# RoPi_2560_0_3.net
KiCad netlist of a schematic drawn in EAGLE
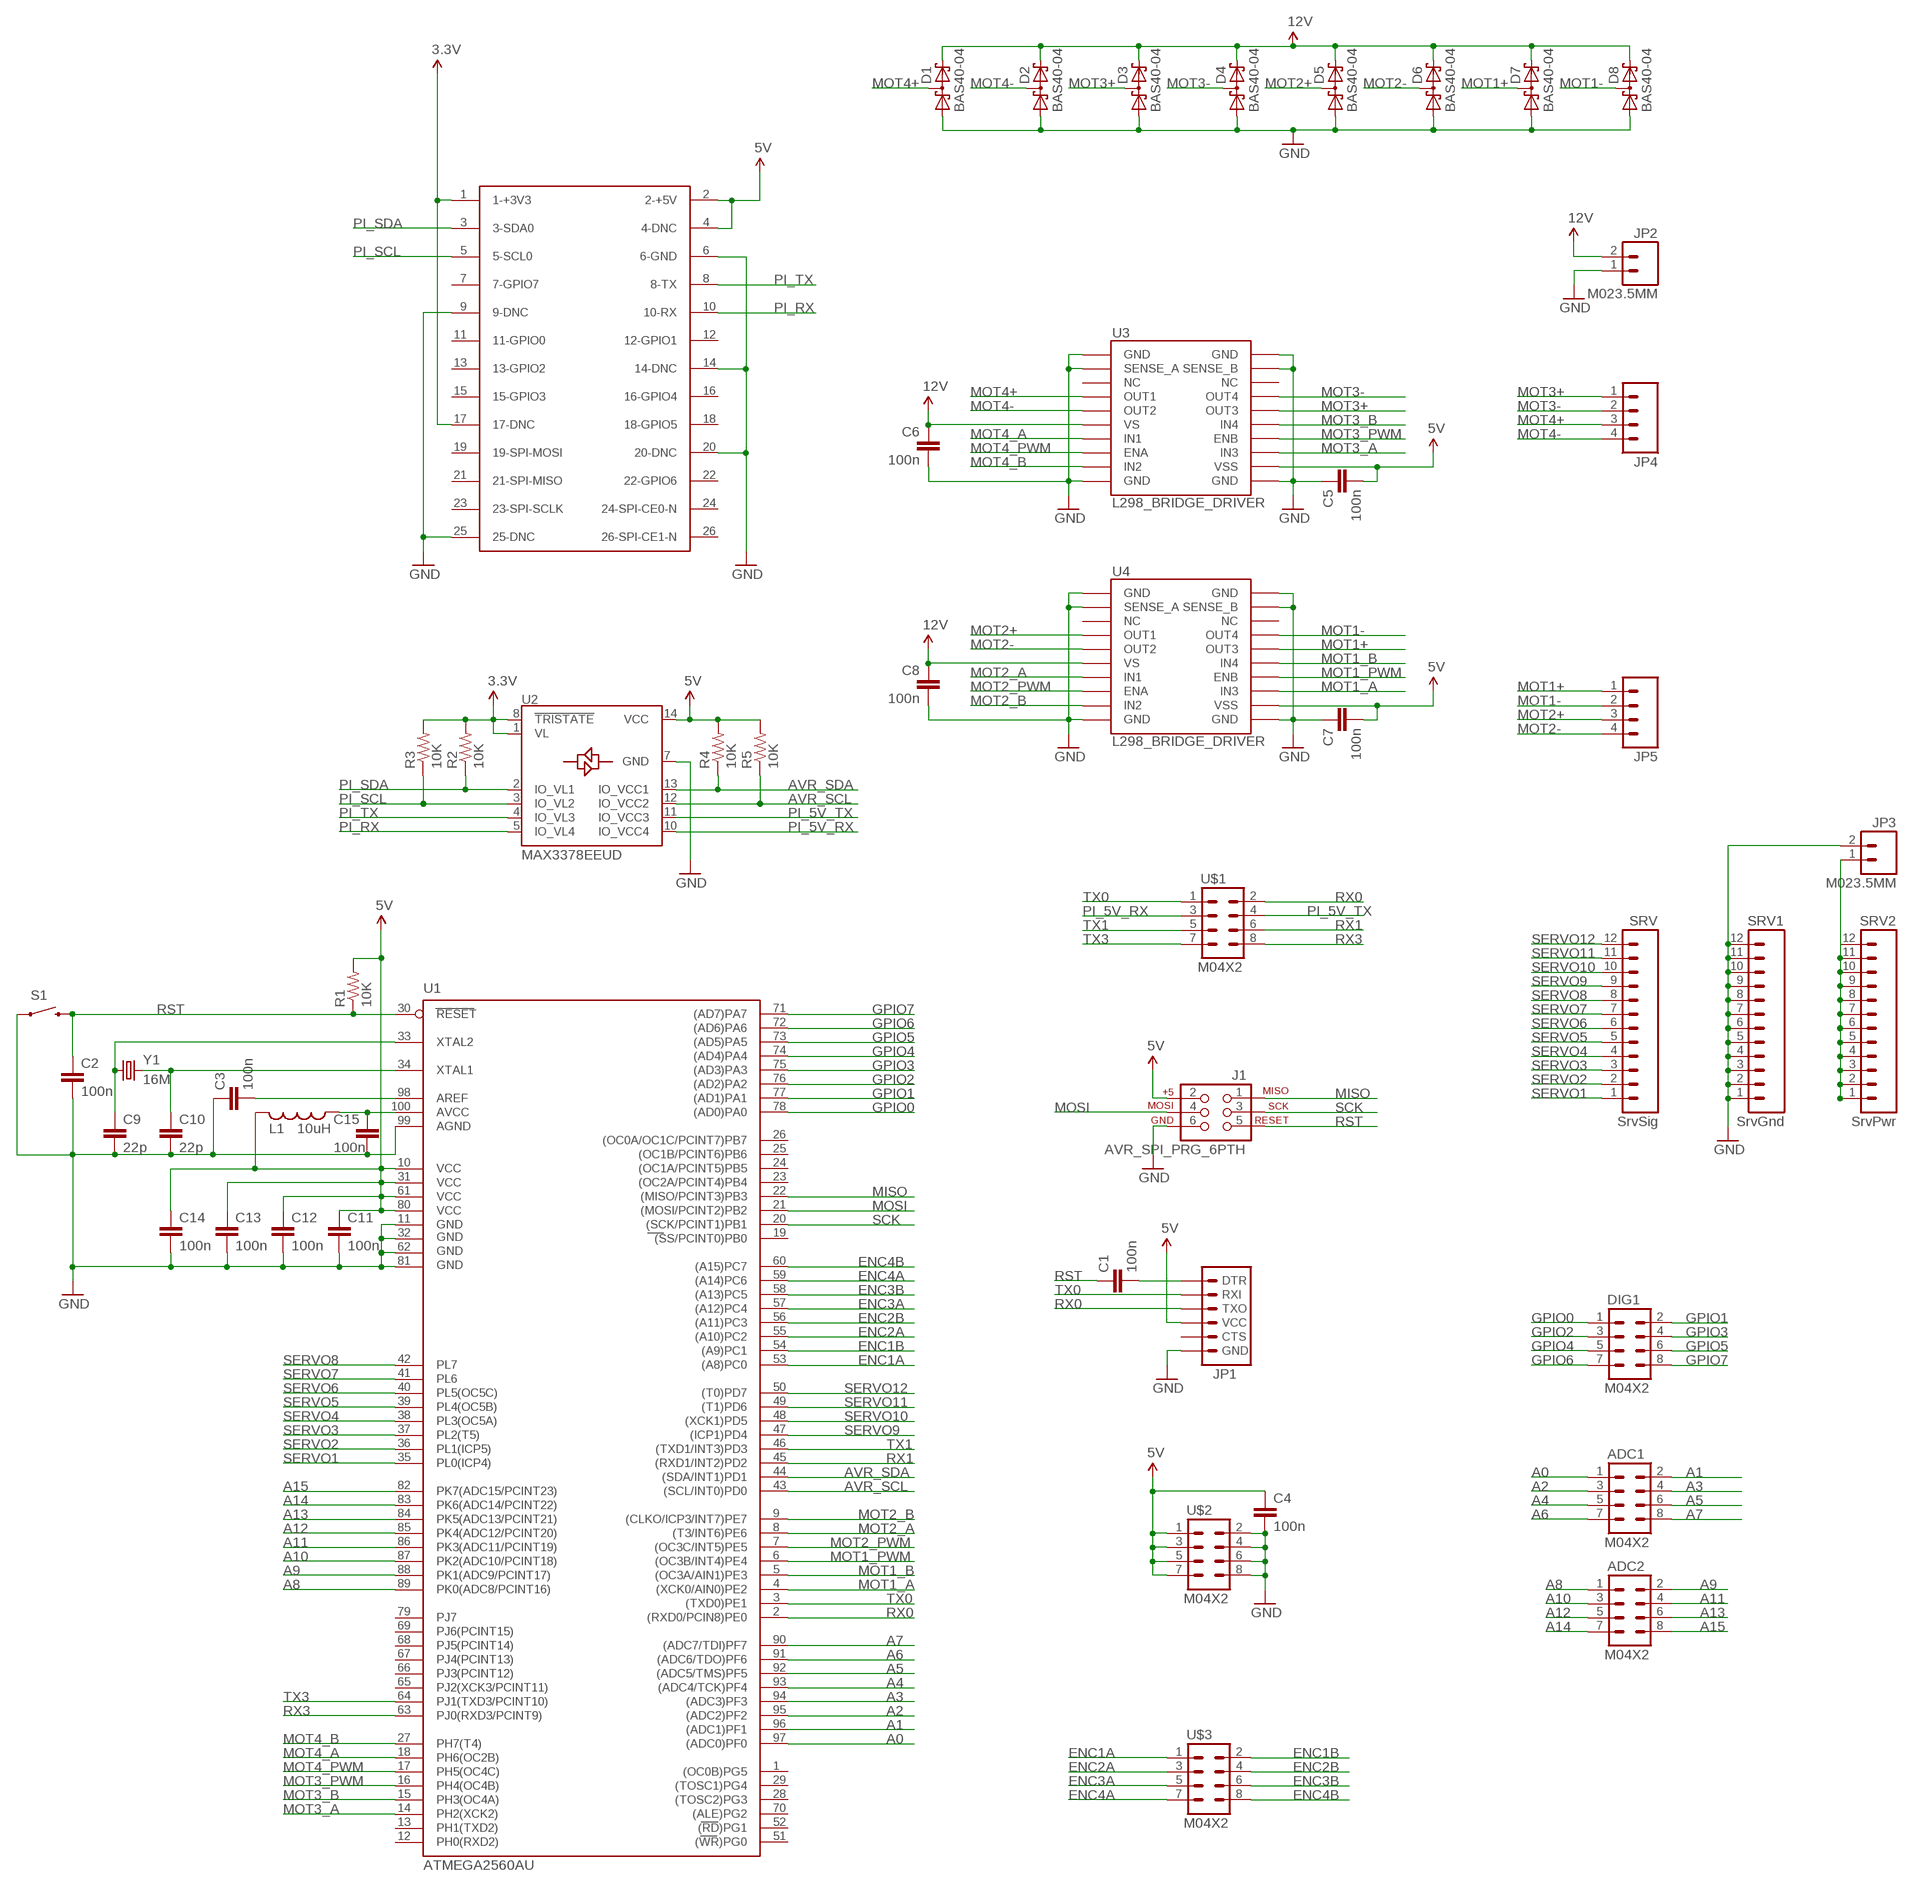
[diagram p0: schematic, sheet 1]

(export (version "E")
  (design (tool "Eeschema 10.0.6"))
  (components
    (comp (ref "ADC1")
      (value "M04X2")
      (footprint "eagle-import:2X4")
      (libsource (lib "eagle-import") (part "M04X2"))
    )
    (comp (ref "ADC2")
      (value "M04X2")
      (footprint "eagle-import:2X4")
      (libsource (lib "eagle-import") (part "M04X2"))
    )
    (comp (ref "C1")
      (value "100n")
      (footprint "eagle-import:0603-CAP")
      (libsource (lib "eagle-import") (part "CAP0603-CAP"))
    )
    (comp (ref "C2")
      (value "100n")
      (footprint "eagle-import:0603-CAP")
      (libsource (lib "eagle-import") (part "CAP0603-CAP"))
    )
    (comp (ref "C3")
      (value "100n")
      (footprint "eagle-import:0603-CAP")
      (libsource (lib "eagle-import") (part "CAP0603-CAP"))
    )
    (comp (ref "C4")
      (value "100n")
      (footprint "eagle-import:0603-CAP")
      (libsource (lib "eagle-import") (part "CAP0603-CAP"))
    )
    (comp (ref "C5")
      (value "100n")
      (footprint "eagle-import:0603-CAP")
      (libsource (lib "eagle-import") (part "CAP0603-CAP"))
    )
    (comp (ref "C6")
      (value "100n")
      (footprint "eagle-import:0603-CAP")
      (libsource (lib "eagle-import") (part "CAP0603-CAP"))
    )
    (comp (ref "C7")
      (value "100n")
      (footprint "eagle-import:0603-CAP")
      (libsource (lib "eagle-import") (part "CAP0603-CAP"))
    )
    (comp (ref "C8")
      (value "100n")
      (footprint "eagle-import:0603-CAP")
      (libsource (lib "eagle-import") (part "CAP0603-CAP"))
    )
    (comp (ref "C9")
      (value "22p")
      (footprint "eagle-import:0603-CAP")
      (libsource (lib "eagle-import") (part "CAP0603-CAP"))
    )
    (comp (ref "C10")
      (value "22p")
      (footprint "eagle-import:0603-CAP")
      (libsource (lib "eagle-import") (part "CAP0603-CAP"))
    )
    (comp (ref "C11")
      (value "100n")
      (footprint "eagle-import:0603-CAP")
      (libsource (lib "eagle-import") (part "CAP0603-CAP"))
    )
    (comp (ref "C12")
      (value "100n")
      (footprint "eagle-import:0603-CAP")
      (libsource (lib "eagle-import") (part "CAP0603-CAP"))
    )
    (comp (ref "C13")
      (value "100n")
      (footprint "eagle-import:0603-CAP")
      (libsource (lib "eagle-import") (part "CAP0603-CAP"))
    )
    (comp (ref "C14")
      (value "100n")
      (footprint "eagle-import:0603-CAP")
      (libsource (lib "eagle-import") (part "CAP0603-CAP"))
    )
    (comp (ref "C15")
      (value "100n")
      (footprint "eagle-import:0603-CAP")
      (libsource (lib "eagle-import") (part "CAP0603-CAP"))
    )
    (comp (ref "D1")
      (value "BAS40-04")
      (footprint "eagle-import:SOT23")
      (libsource (lib "eagle-import") (part "BAS40-04"))
    )
    (comp (ref "D2")
      (value "BAS40-04")
      (footprint "eagle-import:SOT23")
      (libsource (lib "eagle-import") (part "BAS40-04"))
    )
    (comp (ref "D3")
      (value "BAS40-04")
      (footprint "eagle-import:SOT23")
      (libsource (lib "eagle-import") (part "BAS40-04"))
    )
    (comp (ref "D4")
      (value "BAS40-04")
      (footprint "eagle-import:SOT23")
      (libsource (lib "eagle-import") (part "BAS40-04"))
    )
    (comp (ref "D5")
      (value "BAS40-04")
      (footprint "eagle-import:SOT23")
      (libsource (lib "eagle-import") (part "BAS40-04"))
    )
    (comp (ref "D6")
      (value "BAS40-04")
      (footprint "eagle-import:SOT23")
      (libsource (lib "eagle-import") (part "BAS40-04"))
    )
    (comp (ref "D7")
      (value "BAS40-04")
      (footprint "eagle-import:SOT23")
      (libsource (lib "eagle-import") (part "BAS40-04"))
    )
    (comp (ref "D8")
      (value "BAS40-04")
      (footprint "eagle-import:SOT23")
      (libsource (lib "eagle-import") (part "BAS40-04"))
    )
    (comp (ref "DIG1")
      (value "M04X2")
      (footprint "eagle-import:2X4")
      (libsource (lib "eagle-import") (part "M04X2"))
    )
    (comp (ref "J1")
      (value "AVR_SPI_PRG_6PTH")
      (footprint "eagle-import:2X3")
      (libsource (lib "eagle-import") (part "AVR_SPI_PRG_6PTH"))
    )
    (comp (ref "JP1")
      (value "ARDUINO_SERIAL_PROGRAMSMD")
      (footprint "eagle-import:1X06-SMD")
      (libsource (lib "eagle-import") (part "ARDUINO_SERIAL_PROGRAMSMD"))
    )
    (comp (ref "JP2")
      (value "M023.5MM")
      (footprint "eagle-import:SCREWTERMINAL-3.5MM-2")
      (libsource (lib "eagle-import") (part "M023.5MM"))
    )
    (comp (ref "JP3")
      (value "M023.5MM")
      (footprint "eagle-import:SCREWTERMINAL-3.5MM-2")
      (libsource (lib "eagle-import") (part "M023.5MM"))
    )
    (comp (ref "JP4")
      (value "M04SCREW")
      (footprint "eagle-import:SCREWTERMINAL-3.5MM-4")
      (libsource (lib "eagle-import") (part "M04SCREW"))
    )
    (comp (ref "JP5")
      (value "M04SCREW")
      (footprint "eagle-import:SCREWTERMINAL-3.5MM-4")
      (libsource (lib "eagle-import") (part "M04SCREW"))
    )
    (comp (ref "L1")
      (value "10uH")
      (footprint "eagle-import:R0603")
      (libsource (lib "eagle-import") (part "L-US"))
    )
    (comp (ref "PI")
      (value "RASPBERRY-PI")
      (footprint "eagle-import:RASPBERRY-PI")
      (libsource (lib "eagle-import") (part "RASPBERRY-PI"))
    )
    (comp (ref "R1")
      (value "10K")
      (footprint "eagle-import:0603-RES")
      (libsource (lib "eagle-import") (part "RESISTOR0603-RES"))
    )
    (comp (ref "R2")
      (value "10K")
      (footprint "eagle-import:0603-RES")
      (libsource (lib "eagle-import") (part "RESISTOR0603-RES"))
    )
    (comp (ref "R3")
      (value "10K")
      (footprint "eagle-import:0603-RES")
      (libsource (lib "eagle-import") (part "RESISTOR0603-RES"))
    )
    (comp (ref "R4")
      (value "10K")
      (footprint "eagle-import:0603-RES")
      (libsource (lib "eagle-import") (part "RESISTOR0603-RES"))
    )
    (comp (ref "R5")
      (value "10K")
      (footprint "eagle-import:0603-RES")
      (libsource (lib "eagle-import") (part "RESISTOR0603-RES"))
    )
    (comp (ref "S1")
      (value "SWITCH-MOMENTARY-2SMD-4")
      (footprint "eagle-import:TACTILE_SWITCH_TALL")
      (libsource (lib "eagle-import") (part "SWITCH-MOMENTARY-2SMD-4"))
    )
    (comp (ref "SRV")
      (value "SrvSig")
      (footprint "eagle-import:1X12")
      (libsource (lib "eagle-import") (part "M12PTH"))
    )
    (comp (ref "SRV1")
      (value "SrvGnd")
      (footprint "eagle-import:1X12")
      (libsource (lib "eagle-import") (part "M12PTH"))
    )
    (comp (ref "SRV2")
      (value "SrvPwr")
      (footprint "eagle-import:1X12")
      (libsource (lib "eagle-import") (part "M12PTH"))
    )
    (comp (ref "U$1")
      (value "M04X2")
      (footprint "eagle-import:2X4")
      (libsource (lib "eagle-import") (part "M04X2"))
    )
    (comp (ref "U$2")
      (value "M04X2")
      (footprint "eagle-import:2X4")
      (libsource (lib "eagle-import") (part "M04X2"))
    )
    (comp (ref "U$3")
      (value "M04X2")
      (footprint "eagle-import:2X4")
      (libsource (lib "eagle-import") (part "M04X2"))
    )
    (comp (ref "U1")
      (value "ATMEGA2560AU")
      (footprint "eagle-import:TQFP100")
      (libsource (lib "eagle-import") (part "ATMEGA2560AU"))
    )
    (comp (ref "U2")
      (value "MAX3378EEUD")
      (footprint "eagle-import:TSSOP14")
      (libsource (lib "eagle-import") (part "MAX3378EEUD"))
    )
    (comp (ref "U3")
      (value "L298_BRIDGE_DRIVER")
      (footprint "eagle-import:POWERSO20")
      (libsource (lib "eagle-import") (part "L298_BRIDGE_DRIVER"))
    )
    (comp (ref "U4")
      (value "L298_BRIDGE_DRIVER")
      (footprint "eagle-import:POWERSO20")
      (libsource (lib "eagle-import") (part "L298_BRIDGE_DRIVER"))
    )
    (comp (ref "Y1")
      (value "16M")
      (footprint "eagle-import:HC49UP")
      (libsource (lib "eagle-import") (part "CRYSTALSMD"))
    )
  )
  (nets
    (net (code "1") (name "/A0") (class "Default")
      (node (ref "ADC1") (pin "1") (pinfunction "1_1") (pintype "passive"))
      (node (ref "U1") (pin "97") (pinfunction "(ADC0)PF0_97") (pintype "bidirectional"))
    )
    (net (code "2") (name "/A1") (class "Default")
      (node (ref "ADC1") (pin "2") (pinfunction "2_2") (pintype "passive"))
      (node (ref "U1") (pin "96") (pinfunction "(ADC1)PF1_96") (pintype "bidirectional"))
    )
    (net (code "3") (name "/A2") (class "Default")
      (node (ref "ADC1") (pin "3") (pinfunction "3_3") (pintype "passive"))
      (node (ref "U1") (pin "95") (pinfunction "(ADC2)PF2_95") (pintype "bidirectional"))
    )
    (net (code "4") (name "/A3") (class "Default")
      (node (ref "ADC1") (pin "4") (pinfunction "4_4") (pintype "passive"))
      (node (ref "U1") (pin "94") (pinfunction "(ADC3)PF3_94") (pintype "bidirectional"))
    )
    (net (code "5") (name "/A4") (class "Default")
      (node (ref "ADC1") (pin "5") (pinfunction "5_5") (pintype "passive"))
      (node (ref "U1") (pin "93") (pinfunction "(ADC4/TCK)PF4_93") (pintype "bidirectional"))
    )
    (net (code "6") (name "/A5") (class "Default")
      (node (ref "ADC1") (pin "6") (pinfunction "6_6") (pintype "passive"))
      (node (ref "U1") (pin "92") (pinfunction "(ADC5/TMS)PF5_92") (pintype "bidirectional"))
    )
    (net (code "7") (name "/A6") (class "Default")
      (node (ref "ADC1") (pin "7") (pinfunction "7_7") (pintype "passive"))
      (node (ref "U1") (pin "91") (pinfunction "(ADC6/TDO)PF6_91") (pintype "bidirectional"))
    )
    (net (code "8") (name "/A7") (class "Default")
      (node (ref "ADC1") (pin "8") (pinfunction "8_8") (pintype "passive"))
      (node (ref "U1") (pin "90") (pinfunction "(ADC7/TDI)PF7_90") (pintype "bidirectional"))
    )
    (net (code "9") (name "/A8") (class "Default")
      (node (ref "ADC2") (pin "1") (pinfunction "1_1") (pintype "passive"))
      (node (ref "U1") (pin "89") (pinfunction "PK0(ADC8/PCINT16)_89") (pintype "bidirectional"))
    )
    (net (code "10") (name "/A9") (class "Default")
      (node (ref "ADC2") (pin "2") (pinfunction "2_2") (pintype "passive"))
      (node (ref "U1") (pin "88") (pinfunction "PK1(ADC9/PCINT17)_88") (pintype "bidirectional"))
    )
    (net (code "11") (name "/A10") (class "Default")
      (node (ref "ADC2") (pin "3") (pinfunction "3_3") (pintype "passive"))
      (node (ref "U1") (pin "87") (pinfunction "PK2(ADC10/PCINT18)_87") (pintype "bidirectional"))
    )
    (net (code "12") (name "/A11") (class "Default")
      (node (ref "ADC2") (pin "4") (pinfunction "4_4") (pintype "passive"))
      (node (ref "U1") (pin "86") (pinfunction "PK3(ADC11/PCINT19)_86") (pintype "bidirectional"))
    )
    (net (code "13") (name "/A12") (class "Default")
      (node (ref "ADC2") (pin "5") (pinfunction "5_5") (pintype "passive"))
      (node (ref "U1") (pin "85") (pinfunction "PK4(ADC12/PCINT20)_85") (pintype "bidirectional"))
    )
    (net (code "14") (name "/A13") (class "Default")
      (node (ref "ADC2") (pin "6") (pinfunction "6_6") (pintype "passive"))
      (node (ref "U1") (pin "84") (pinfunction "PK5(ADC13/PCINT21)_84") (pintype "bidirectional"))
    )
    (net (code "15") (name "/A14") (class "Default")
      (node (ref "ADC2") (pin "7") (pinfunction "7_7") (pintype "passive"))
      (node (ref "U1") (pin "83") (pinfunction "PK6(ADC14/PCINT22)_83") (pintype "bidirectional"))
    )
    (net (code "16") (name "/A15") (class "Default")
      (node (ref "ADC2") (pin "8") (pinfunction "8_8") (pintype "passive"))
      (node (ref "U1") (pin "82") (pinfunction "PK7(ADC15/PCINT23)_82") (pintype "bidirectional"))
    )
    (net (code "17") (name "/AVR_SCL") (class "Default")
      (node (ref "R5") (pin "1") (pinfunction "1_1") (pintype "passive"))
      (node (ref "U1") (pin "43") (pinfunction "(SCL/INT0)PD0_43") (pintype "bidirectional"))
      (node (ref "U2") (pin "12") (pinfunction "IO_VCC2_12") (pintype "bidirectional"))
    )
    (net (code "18") (name "/AVR_SDA") (class "Default")
      (node (ref "R4") (pin "1") (pinfunction "1_1") (pintype "passive"))
      (node (ref "U1") (pin "44") (pinfunction "(SDA/INT1)PD1_44") (pintype "bidirectional"))
      (node (ref "U2") (pin "13") (pinfunction "IO_VCC1_13") (pintype "bidirectional"))
    )
    (net (code "19") (name "/ENC1A") (class "Default")
      (node (ref "U$3") (pin "1") (pinfunction "1_1") (pintype "passive"))
      (node (ref "U1") (pin "53") (pinfunction "(A8)PC0_53") (pintype "bidirectional"))
    )
    (net (code "20") (name "/ENC1B") (class "Default")
      (node (ref "U$3") (pin "2") (pinfunction "2_2") (pintype "passive"))
      (node (ref "U1") (pin "54") (pinfunction "(A9)PC1_54") (pintype "bidirectional"))
    )
    (net (code "21") (name "/ENC2A") (class "Default")
      (node (ref "U$3") (pin "3") (pinfunction "3_3") (pintype "passive"))
      (node (ref "U1") (pin "55") (pinfunction "(A10)PC2_55") (pintype "bidirectional"))
    )
    (net (code "22") (name "/ENC2B") (class "Default")
      (node (ref "U$3") (pin "4") (pinfunction "4_4") (pintype "passive"))
      (node (ref "U1") (pin "56") (pinfunction "(A11)PC3_56") (pintype "bidirectional"))
    )
    (net (code "23") (name "/ENC3A") (class "Default")
      (node (ref "U$3") (pin "5") (pinfunction "5_5") (pintype "passive"))
      (node (ref "U1") (pin "57") (pinfunction "(A12)PC4_57") (pintype "bidirectional"))
    )
    (net (code "24") (name "/ENC3B") (class "Default")
      (node (ref "U$3") (pin "6") (pinfunction "6_6") (pintype "passive"))
      (node (ref "U1") (pin "58") (pinfunction "(A13)PC5_58") (pintype "bidirectional"))
    )
    (net (code "25") (name "/ENC4A") (class "Default")
      (node (ref "U$3") (pin "7") (pinfunction "7_7") (pintype "passive"))
      (node (ref "U1") (pin "59") (pinfunction "(A14)PC6_59") (pintype "bidirectional"))
    )
    (net (code "26") (name "/ENC4B") (class "Default")
      (node (ref "U$3") (pin "8") (pinfunction "8_8") (pintype "passive"))
      (node (ref "U1") (pin "60") (pinfunction "(A15)PC7_60") (pintype "bidirectional"))
    )
    (net (code "27") (name "/GPIO0") (class "Default")
      (node (ref "DIG1") (pin "1") (pinfunction "1_1") (pintype "passive"))
      (node (ref "U1") (pin "78") (pinfunction "(AD0)PA0_78") (pintype "bidirectional"))
    )
    (net (code "28") (name "/GPIO1") (class "Default")
      (node (ref "DIG1") (pin "2") (pinfunction "2_2") (pintype "passive"))
      (node (ref "U1") (pin "77") (pinfunction "(AD1)PA1_77") (pintype "bidirectional"))
    )
    (net (code "29") (name "/GPIO2") (class "Default")
      (node (ref "DIG1") (pin "3") (pinfunction "3_3") (pintype "passive"))
      (node (ref "U1") (pin "76") (pinfunction "(AD2)PA2_76") (pintype "bidirectional"))
    )
    (net (code "30") (name "/GPIO3") (class "Default")
      (node (ref "DIG1") (pin "4") (pinfunction "4_4") (pintype "passive"))
      (node (ref "U1") (pin "75") (pinfunction "(AD3)PA3_75") (pintype "bidirectional"))
    )
    (net (code "31") (name "/GPIO4") (class "Default")
      (node (ref "DIG1") (pin "5") (pinfunction "5_5") (pintype "passive"))
      (node (ref "U1") (pin "74") (pinfunction "(AD4)PA4_74") (pintype "bidirectional"))
    )
    (net (code "32") (name "/GPIO5") (class "Default")
      (node (ref "DIG1") (pin "6") (pinfunction "6_6") (pintype "passive"))
      (node (ref "U1") (pin "73") (pinfunction "(AD5)PA5_73") (pintype "bidirectional"))
    )
    (net (code "33") (name "/GPIO6") (class "Default")
      (node (ref "DIG1") (pin "7") (pinfunction "7_7") (pintype "passive"))
      (node (ref "U1") (pin "72") (pinfunction "(AD6)PA6_72") (pintype "bidirectional"))
    )
    (net (code "34") (name "/GPIO7") (class "Default")
      (node (ref "DIG1") (pin "8") (pinfunction "8_8") (pintype "passive"))
      (node (ref "U1") (pin "71") (pinfunction "(AD7)PA7_71") (pintype "bidirectional"))
    )
    (net (code "35") (name "/MISO") (class "Default")
      (node (ref "J1") (pin "1") (pinfunction "1_1") (pintype "passive"))
      (node (ref "U1") (pin "22") (pinfunction "(MISO/PCINT3)PB3_22") (pintype "bidirectional"))
    )
    (net (code "36") (name "/MOSI") (class "Default")
      (node (ref "J1") (pin "4") (pinfunction "4_4") (pintype "passive"))
      (node (ref "U1") (pin "21") (pinfunction "(MOSI/PCINT2)PB2_21") (pintype "bidirectional"))
    )
    (net (code "37") (name "/MOT1+") (class "Default")
      (node (ref "D7") (pin "3") (pinfunction "C1A2_3") (pintype "passive"))
      (node (ref "JP5") (pin "1") (pinfunction "1_1") (pintype "passive"))
      (node (ref "U4") (pin "16") (pinfunction "OUT3_16") (pintype "bidirectional"))
    )
    (net (code "38") (name "/MOT1-") (class "Default")
      (node (ref "D8") (pin "3") (pinfunction "C1A2_3") (pintype "passive"))
      (node (ref "JP5") (pin "2") (pinfunction "2_2") (pintype "passive"))
      (node (ref "U4") (pin "17") (pinfunction "OUT4_17") (pintype "bidirectional"))
    )
    (net (code "39") (name "/MOT1_A") (class "Default")
      (node (ref "U1") (pin "4") (pinfunction "(XCK0/AIN0)PE2_4") (pintype "bidirectional"))
      (node (ref "U4") (pin "13") (pinfunction "IN3_13") (pintype "bidirectional"))
    )
    (net (code "40") (name "/MOT1_B") (class "Default")
      (node (ref "U1") (pin "5") (pinfunction "(OC3A/AIN1)PE3_5") (pintype "bidirectional"))
      (node (ref "U4") (pin "15") (pinfunction "IN4_15") (pintype "bidirectional"))
    )
    (net (code "41") (name "/MOT1_PWM") (class "Default")
      (node (ref "U1") (pin "6") (pinfunction "(OC3B/INT4)PE4_6") (pintype "bidirectional"))
      (node (ref "U4") (pin "14") (pinfunction "ENB_14") (pintype "bidirectional"))
    )
    (net (code "42") (name "/MOT2+") (class "Default")
      (node (ref "D5") (pin "3") (pinfunction "C1A2_3") (pintype "passive"))
      (node (ref "JP5") (pin "3") (pinfunction "3_3") (pintype "passive"))
      (node (ref "U4") (pin "4") (pinfunction "OUT1_4") (pintype "bidirectional"))
    )
    (net (code "43") (name "/MOT2-") (class "Default")
      (node (ref "D6") (pin "3") (pinfunction "C1A2_3") (pintype "passive"))
      (node (ref "JP5") (pin "4") (pinfunction "4_4") (pintype "passive"))
      (node (ref "U4") (pin "5") (pinfunction "OUT2_5") (pintype "bidirectional"))
    )
    (net (code "44") (name "/MOT2_A") (class "Default")
      (node (ref "U1") (pin "8") (pinfunction "(T3/INT6)PE6_8") (pintype "bidirectional"))
      (node (ref "U4") (pin "7") (pinfunction "IN1_7") (pintype "bidirectional"))
    )
    (net (code "45") (name "/MOT2_B") (class "Default")
      (node (ref "U1") (pin "9") (pinfunction "(CLKO/ICP3/INT7)PE7_9") (pintype "bidirectional"))
      (node (ref "U4") (pin "9") (pinfunction "IN2_9") (pintype "bidirectional"))
    )
    (net (code "46") (name "/MOT2_PWM") (class "Default")
      (node (ref "U1") (pin "7") (pinfunction "(OC3C/INT5)PE5_7") (pintype "bidirectional"))
      (node (ref "U4") (pin "8") (pinfunction "ENA_8") (pintype "bidirectional"))
    )
    (net (code "47") (name "/MOT3+") (class "Default")
      (node (ref "D3") (pin "3") (pinfunction "C1A2_3") (pintype "passive"))
      (node (ref "JP4") (pin "1") (pinfunction "1_1") (pintype "passive"))
      (node (ref "U3") (pin "16") (pinfunction "OUT3_16") (pintype "bidirectional"))
    )
    (net (code "48") (name "/MOT3-") (class "Default")
      (node (ref "D4") (pin "3") (pinfunction "C1A2_3") (pintype "passive"))
      (node (ref "JP4") (pin "2") (pinfunction "2_2") (pintype "passive"))
      (node (ref "U3") (pin "17") (pinfunction "OUT4_17") (pintype "bidirectional"))
    )
    (net (code "49") (name "/MOT3_A") (class "Default")
      (node (ref "U1") (pin "14") (pinfunction "PH2(XCK2)_14") (pintype "bidirectional"))
      (node (ref "U3") (pin "13") (pinfunction "IN3_13") (pintype "bidirectional"))
    )
    (net (code "50") (name "/MOT3_B") (class "Default")
      (node (ref "U1") (pin "15") (pinfunction "PH3(OC4A)_15") (pintype "bidirectional"))
      (node (ref "U3") (pin "15") (pinfunction "IN4_15") (pintype "bidirectional"))
    )
    (net (code "51") (name "/MOT3_PWM") (class "Default")
      (node (ref "U1") (pin "16") (pinfunction "PH4(OC4B)_16") (pintype "bidirectional"))
      (node (ref "U3") (pin "14") (pinfunction "ENB_14") (pintype "bidirectional"))
    )
    (net (code "52") (name "/MOT4+") (class "Default")
      (node (ref "D1") (pin "3") (pinfunction "C1A2_3") (pintype "passive"))
      (node (ref "JP4") (pin "3") (pinfunction "3_3") (pintype "passive"))
      (node (ref "U3") (pin "4") (pinfunction "OUT1_4") (pintype "bidirectional"))
    )
    (net (code "53") (name "/MOT4-") (class "Default")
      (node (ref "D2") (pin "3") (pinfunction "C1A2_3") (pintype "passive"))
      (node (ref "JP4") (pin "4") (pinfunction "4_4") (pintype "passive"))
      (node (ref "U3") (pin "5") (pinfunction "OUT2_5") (pintype "bidirectional"))
    )
    (net (code "54") (name "/MOT4_A") (class "Default")
      (node (ref "U1") (pin "18") (pinfunction "PH6(OC2B)_18") (pintype "bidirectional"))
      (node (ref "U3") (pin "7") (pinfunction "IN1_7") (pintype "bidirectional"))
    )
    (net (code "55") (name "/MOT4_B") (class "Default")
      (node (ref "U1") (pin "27") (pinfunction "PH7(T4)_27") (pintype "bidirectional"))
      (node (ref "U3") (pin "9") (pinfunction "IN2_9") (pintype "bidirectional"))
    )
    (net (code "56") (name "/MOT4_PWM") (class "Default")
      (node (ref "U1") (pin "17") (pinfunction "PH5(OC4C)_17") (pintype "bidirectional"))
      (node (ref "U3") (pin "8") (pinfunction "ENA_8") (pintype "bidirectional"))
    )
    (net (code "57") (name "/PI_5V_RX") (class "Default")
      (node (ref "U$1") (pin "3") (pinfunction "3_3") (pintype "passive"))
      (node (ref "U2") (pin "10") (pinfunction "IO_VCC4_10") (pintype "bidirectional"))
    )
    (net (code "58") (name "/PI_5V_TX") (class "Default")
      (node (ref "U$1") (pin "4") (pinfunction "4_4") (pintype "passive"))
      (node (ref "U2") (pin "11") (pinfunction "IO_VCC3_11") (pintype "bidirectional"))
    )
    (net (code "59") (name "/PI_RX") (class "Default")
      (node (ref "PI") (pin "10") (pinfunction "10-RX_10") (pintype "bidirectional"))
      (node (ref "U2") (pin "5") (pinfunction "IO_VL4_5") (pintype "bidirectional"))
    )
    (net (code "60") (name "/PI_SCL") (class "Default")
      (node (ref "PI") (pin "5") (pinfunction "5-SCL0_5") (pintype "bidirectional"))
      (node (ref "R3") (pin "1") (pinfunction "1_1") (pintype "passive"))
      (node (ref "U2") (pin "3") (pinfunction "IO_VL2_3") (pintype "bidirectional"))
    )
    (net (code "61") (name "/PI_SDA") (class "Default")
      (node (ref "PI") (pin "3") (pinfunction "3-SDA0_3") (pintype "bidirectional"))
      (node (ref "R2") (pin "1") (pinfunction "1_1") (pintype "passive"))
      (node (ref "U2") (pin "2") (pinfunction "IO_VL1_2") (pintype "bidirectional"))
    )
    (net (code "62") (name "/PI_TX") (class "Default")
      (node (ref "PI") (pin "8") (pinfunction "8-TX_8") (pintype "bidirectional"))
      (node (ref "U2") (pin "4") (pinfunction "IO_VL3_4") (pintype "bidirectional"))
    )
    (net (code "63") (name "/RST") (class "Default")
      (node (ref "C1") (pin "1") (pinfunction "1_1") (pintype "passive"))
      (node (ref "C2") (pin "1") (pinfunction "1_1") (pintype "passive"))
      (node (ref "J1") (pin "5") (pinfunction "5_5") (pintype "passive"))
      (node (ref "R1") (pin "1") (pinfunction "1_1") (pintype "passive"))
      (node (ref "S1") (pin "B2") (pinfunction "2_B2") (pintype "passive"))
      (node (ref "U1") (pin "30") (pinfunction "RESET_30") (pintype "input"))
    )
    (net (code "64") (name "/RX0") (class "Default")
      (node (ref "JP1") (pin "3") (pinfunction "TXO_3") (pintype "passive"))
      (node (ref "U$1") (pin "2") (pinfunction "2_2") (pintype "passive"))
      (node (ref "U1") (pin "2") (pinfunction "(RXD0/PCIN8)PE0_2") (pintype "bidirectional"))
    )
    (net (code "65") (name "/RX1") (class "Default")
      (node (ref "U$1") (pin "6") (pinfunction "6_6") (pintype "passive"))
      (node (ref "U1") (pin "45") (pinfunction "(RXD1/INT2)PD2_45") (pintype "bidirectional"))
    )
    (net (code "66") (name "/RX3") (class "Default")
      (node (ref "U$1") (pin "8") (pinfunction "8_8") (pintype "passive"))
      (node (ref "U1") (pin "63") (pinfunction "PJ0(RXD3/PCINT9)_63") (pintype "bidirectional"))
    )
    (net (code "67") (name "/SCK") (class "Default")
      (node (ref "J1") (pin "3") (pinfunction "3_3") (pintype "passive"))
      (node (ref "U1") (pin "20") (pinfunction "(SCK/PCINT1)PB1_20") (pintype "bidirectional"))
    )
    (net (code "68") (name "/SERVO1") (class "Default")
      (node (ref "SRV") (pin "1") (pinfunction "1_1") (pintype "passive"))
      (node (ref "U1") (pin "35") (pinfunction "PL0(ICP4)_35") (pintype "bidirectional"))
    )
    (net (code "69") (name "/SERVO2") (class "Default")
      (node (ref "SRV") (pin "2") (pinfunction "2_2") (pintype "passive"))
      (node (ref "U1") (pin "36") (pinfunction "PL1(ICP5)_36") (pintype "bidirectional"))
    )
    (net (code "70") (name "/SERVO3") (class "Default")
      (node (ref "SRV") (pin "3") (pinfunction "3_3") (pintype "passive"))
      (node (ref "U1") (pin "37") (pinfunction "PL2(T5)_37") (pintype "bidirectional"))
    )
    (net (code "71") (name "/SERVO4") (class "Default")
      (node (ref "SRV") (pin "4") (pinfunction "4_4") (pintype "passive"))
      (node (ref "U1") (pin "38") (pinfunction "PL3(OC5A)_38") (pintype "bidirectional"))
    )
    (net (code "72") (name "/SERVO5") (class "Default")
      (node (ref "SRV") (pin "5") (pinfunction "5_5") (pintype "passive"))
      (node (ref "U1") (pin "39") (pinfunction "PL4(OC5B)_39") (pintype "bidirectional"))
    )
    (net (code "73") (name "/SERVO6") (class "Default")
      (node (ref "SRV") (pin "6") (pinfunction "6_6") (pintype "passive"))
      (node (ref "U1") (pin "40") (pinfunction "PL5(OC5C)_40") (pintype "bidirectional"))
    )
    (net (code "74") (name "/SERVO7") (class "Default")
      (node (ref "SRV") (pin "7") (pinfunction "7_7") (pintype "passive"))
      (node (ref "U1") (pin "41") (pinfunction "PL6_41") (pintype "bidirectional"))
    )
    (net (code "75") (name "/SERVO8") (class "Default")
      (node (ref "SRV") (pin "8") (pinfunction "8_8") (pintype "passive"))
      (node (ref "U1") (pin "42") (pinfunction "PL7_42") (pintype "bidirectional"))
    )
    (net (code "76") (name "/SERVO9") (class "Default")
      (node (ref "SRV") (pin "9") (pinfunction "9_9") (pintype "passive"))
      (node (ref "U1") (pin "47") (pinfunction "(ICP1)PD4_47") (pintype "bidirectional"))
    )
    (net (code "77") (name "/SERVO10") (class "Default")
      (node (ref "SRV") (pin "10") (pinfunction "10_10") (pintype "passive"))
      (node (ref "U1") (pin "48") (pinfunction "(XCK1)PD5_48") (pintype "bidirectional"))
    )
    (net (code "78") (name "/SERVO11") (class "Default")
      (node (ref "SRV") (pin "11") (pinfunction "11_11") (pintype "passive"))
      (node (ref "U1") (pin "49") (pinfunction "(T1)PD6_49") (pintype "bidirectional"))
    )
    (net (code "79") (name "/SERVO12") (class "Default")
      (node (ref "SRV") (pin "12") (pinfunction "12_12") (pintype "passive"))
      (node (ref "U1") (pin "50") (pinfunction "(T0)PD7_50") (pintype "bidirectional"))
    )
    (net (code "80") (name "/TX0") (class "Default")
      (node (ref "JP1") (pin "2") (pinfunction "RXI_2") (pintype "passive"))
      (node (ref "U$1") (pin "1") (pinfunction "1_1") (pintype "passive"))
      (node (ref "U1") (pin "3") (pinfunction "(TXD0)PE1_3") (pintype "bidirectional"))
    )
    (net (code "81") (name "/TX1") (class "Default")
      (node (ref "U$1") (pin "5") (pinfunction "5_5") (pintype "passive"))
      (node (ref "U1") (pin "46") (pinfunction "(TXD1/INT3)PD3_46") (pintype "bidirectional"))
    )
    (net (code "82") (name "/TX3") (class "Default")
      (node (ref "U$1") (pin "7") (pinfunction "7_7") (pintype "passive"))
      (node (ref "U1") (pin "64") (pinfunction "PJ1(TXD3/PCINT10)_64") (pintype "bidirectional"))
    )
    (net (code "83") (name "3.3V") (class "Default")
      (node (ref "PI") (pin "1") (pinfunction "1-+3V3_1") (pintype "bidirectional"))
      (node (ref "PI") (pin "17") (pinfunction "17-DNC_17") (pintype "bidirectional"))
      (node (ref "R2") (pin "2") (pinfunction "2_2") (pintype "passive"))
      (node (ref "R3") (pin "2") (pinfunction "2_2") (pintype "passive"))
      (node (ref "U2") (pin "1") (pinfunction "VL_1") (pintype "power_in"))
      (node (ref "U2") (pin "8") (pinfunction "~{TRISTATE}_8") (pintype "input"))
    )
    (net (code "84") (name "5V") (class "Default")
      (node (ref "C11") (pin "1") (pinfunction "1_1") (pintype "passive"))
      (node (ref "C12") (pin "1") (pinfunction "1_1") (pintype "passive"))
      (node (ref "C13") (pin "1") (pinfunction "1_1") (pintype "passive"))
      (node (ref "C14") (pin "1") (pinfunction "1_1") (pintype "passive"))
      (node (ref "C4") (pin "1") (pinfunction "1_1") (pintype "passive"))
      (node (ref "C5") (pin "2") (pinfunction "2_2") (pintype "passive"))
      (node (ref "C7") (pin "2") (pinfunction "2_2") (pintype "passive"))
      (node (ref "J1") (pin "2") (pinfunction "2_2") (pintype "passive"))
      (node (ref "JP1") (pin "4") (pinfunction "VCC_4") (pintype "passive"))
      (node (ref "L1") (pin "2") (pinfunction "2_2") (pintype "passive"))
      (node (ref "PI") (pin "2") (pinfunction "2-+5V_2") (pintype "bidirectional"))
      (node (ref "PI") (pin "4") (pinfunction "4-DNC_4") (pintype "bidirectional"))
      (node (ref "R1") (pin "2") (pinfunction "2_2") (pintype "passive"))
      (node (ref "R4") (pin "2") (pinfunction "2_2") (pintype "passive"))
      (node (ref "R5") (pin "2") (pinfunction "2_2") (pintype "passive"))
      (node (ref "U$2") (pin "1") (pinfunction "1_1") (pintype "passive"))
      (node (ref "U$2") (pin "3") (pinfunction "3_3") (pintype "passive"))
      (node (ref "U$2") (pin "5") (pinfunction "5_5") (pintype "passive"))
      (node (ref "U$2") (pin "7") (pinfunction "7_7") (pintype "passive"))
      (node (ref "U1") (pin "10") (pinfunction "VCC_10") (pintype "power_in"))
      (node (ref "U1") (pin "31") (pinfunction "VCC1_31") (pintype "power_in"))
      (node (ref "U1") (pin "61") (pinfunction "VCC2_61") (pintype "power_in"))
      (node (ref "U1") (pin "80") (pinfunction "VCC3_80") (pintype "power_in"))
      (node (ref "U2") (pin "14") (pinfunction "VCC_14") (pintype "power_in"))
      (node (ref "U3") (pin "12") (pinfunction "VSS_12") (pintype "bidirectional"))
      (node (ref "U4") (pin "12") (pinfunction "VSS_12") (pintype "bidirectional"))
    )
    (net (code "85") (name "12V") (class "Default")
      (node (ref "C6") (pin "1") (pinfunction "1_1") (pintype "passive"))
      (node (ref "C8") (pin "1") (pinfunction "1_1") (pintype "passive"))
      (node (ref "D1") (pin "2") (pinfunction "C2_2") (pintype "passive"))
      (node (ref "D2") (pin "2") (pinfunction "C2_2") (pintype "passive"))
      (node (ref "D3") (pin "2") (pinfunction "C2_2") (pintype "passive"))
      (node (ref "D4") (pin "2") (pinfunction "C2_2") (pintype "passive"))
      (node (ref "D5") (pin "2") (pinfunction "C2_2") (pintype "passive"))
      (node (ref "D6") (pin "2") (pinfunction "C2_2") (pintype "passive"))
      (node (ref "D7") (pin "2") (pinfunction "C2_2") (pintype "passive"))
      (node (ref "D8") (pin "2") (pinfunction "C2_2") (pintype "passive"))
      (node (ref "JP2") (pin "2") (pinfunction "2_2") (pintype "passive"))
      (node (ref "U3") (pin "6") (pinfunction "VS_6") (pintype "bidirectional"))
      (node (ref "U4") (pin "6") (pinfunction "VS_6") (pintype "bidirectional"))
    )
    (net (code "86") (name "GND") (class "Default")
      (node (ref "C10") (pin "2") (pinfunction "2_2") (pintype "passive"))
      (node (ref "C11") (pin "2") (pinfunction "2_2") (pintype "passive"))
      (node (ref "C12") (pin "2") (pinfunction "2_2") (pintype "passive"))
      (node (ref "C13") (pin "2") (pinfunction "2_2") (pintype "passive"))
      (node (ref "C14") (pin "2") (pinfunction "2_2") (pintype "passive"))
      (node (ref "C15") (pin "2") (pinfunction "2_2") (pintype "passive"))
      (node (ref "C2") (pin "2") (pinfunction "2_2") (pintype "passive"))
      (node (ref "C3") (pin "1") (pinfunction "1_1") (pintype "passive"))
      (node (ref "C4") (pin "2") (pinfunction "2_2") (pintype "passive"))
      (node (ref "C5") (pin "1") (pinfunction "1_1") (pintype "passive"))
      (node (ref "C6") (pin "2") (pinfunction "2_2") (pintype "passive"))
      (node (ref "C7") (pin "1") (pinfunction "1_1") (pintype "passive"))
      (node (ref "C8") (pin "2") (pinfunction "2_2") (pintype "passive"))
      (node (ref "C9") (pin "2") (pinfunction "2_2") (pintype "passive"))
      (node (ref "D1") (pin "1") (pinfunction "A1_1") (pintype "passive"))
      (node (ref "D2") (pin "1") (pinfunction "A1_1") (pintype "passive"))
      (node (ref "D3") (pin "1") (pinfunction "A1_1") (pintype "passive"))
      (node (ref "D4") (pin "1") (pinfunction "A1_1") (pintype "passive"))
      (node (ref "D5") (pin "1") (pinfunction "A1_1") (pintype "passive"))
      (node (ref "D6") (pin "1") (pinfunction "A1_1") (pintype "passive"))
      (node (ref "D7") (pin "1") (pinfunction "A1_1") (pintype "passive"))
      (node (ref "D8") (pin "1") (pinfunction "A1_1") (pintype "passive"))
      (node (ref "J1") (pin "6") (pinfunction "6_6") (pintype "passive"))
      (node (ref "JP1") (pin "6") (pinfunction "GND_6") (pintype "passive"))
      (node (ref "JP2") (pin "1") (pinfunction "1_1") (pintype "passive"))
      (node (ref "JP3") (pin "2") (pinfunction "2_2") (pintype "passive"))
      (node (ref "PI") (pin "14") (pinfunction "14-DNC_14") (pintype "bidirectional"))
      (node (ref "PI") (pin "20") (pinfunction "20-DNC_20") (pintype "bidirectional"))
      (node (ref "PI") (pin "25") (pinfunction "25-DNC_25") (pintype "bidirectional"))
      (node (ref "PI") (pin "6") (pinfunction "6-GND_6") (pintype "bidirectional"))
      (node (ref "PI") (pin "9") (pinfunction "9-DNC_9") (pintype "bidirectional"))
      (node (ref "S1") (pin "A2") (pinfunction "1_A2") (pintype "passive"))
      (node (ref "SRV1") (pin "1") (pinfunction "1_1") (pintype "passive"))
      (node (ref "SRV1") (pin "10") (pinfunction "10_10") (pintype "passive"))
      (node (ref "SRV1") (pin "11") (pinfunction "11_11") (pintype "passive"))
      (node (ref "SRV1") (pin "12") (pinfunction "12_12") (pintype "passive"))
      (node (ref "SRV1") (pin "2") (pinfunction "2_2") (pintype "passive"))
      (node (ref "SRV1") (pin "3") (pinfunction "3_3") (pintype "passive"))
      (node (ref "SRV1") (pin "4") (pinfunction "4_4") (pintype "passive"))
      (node (ref "SRV1") (pin "5") (pinfunction "5_5") (pintype "passive"))
      (node (ref "SRV1") (pin "6") (pinfunction "6_6") (pintype "passive"))
      (node (ref "SRV1") (pin "7") (pinfunction "7_7") (pintype "passive"))
      (node (ref "SRV1") (pin "8") (pinfunction "8_8") (pintype "passive"))
      (node (ref "SRV1") (pin "9") (pinfunction "9_9") (pintype "passive"))
      (node (ref "U$2") (pin "2") (pinfunction "2_2") (pintype "passive"))
      (node (ref "U$2") (pin "4") (pinfunction "4_4") (pintype "passive"))
      (node (ref "U$2") (pin "6") (pinfunction "6_6") (pintype "passive"))
      (node (ref "U$2") (pin "8") (pinfunction "8_8") (pintype "passive"))
      (node (ref "U1") (pin "11") (pinfunction "GND_11") (pintype "power_in"))
      (node (ref "U1") (pin "32") (pinfunction "GND1_32") (pintype "power_in"))
      (node (ref "U1") (pin "62") (pinfunction "GND2_62") (pintype "power_in"))
      (node (ref "U1") (pin "81") (pinfunction "GND3_81") (pintype "power_in"))
      (node (ref "U1") (pin "99") (pinfunction "AGND_99") (pintype "power_in"))
      (node (ref "U2") (pin "7") (pinfunction "GND_7") (pintype "power_in"))
      (node (ref "U3") (pin "1") (pinfunction "GND_1") (pintype "bidirectional"))
      (node (ref "U3") (pin "10") (pinfunction "GND_10") (pintype "bidirectional"))
      (node (ref "U3") (pin "11") (pinfunction "GND_11") (pintype "bidirectional"))
      (node (ref "U3") (pin "19") (pinfunction "SENSE_B_19") (pintype "bidirectional"))
      (node (ref "U3") (pin "2") (pinfunction "SENSE_A_2") (pintype "bidirectional"))
      (node (ref "U3") (pin "20") (pinfunction "GND_20") (pintype "bidirectional"))
      (node (ref "U4") (pin "1") (pinfunction "GND_1") (pintype "bidirectional"))
      (node (ref "U4") (pin "10") (pinfunction "GND_10") (pintype "bidirectional"))
      (node (ref "U4") (pin "11") (pinfunction "GND_11") (pintype "bidirectional"))
      (node (ref "U4") (pin "19") (pinfunction "SENSE_B_19") (pintype "bidirectional"))
      (node (ref "U4") (pin "2") (pinfunction "SENSE_A_2") (pintype "bidirectional"))
      (node (ref "U4") (pin "20") (pinfunction "GND_20") (pintype "bidirectional"))
    )
    (net (code "87") (name "Net-(JP1-DTR)") (class "Default")
      (node (ref "C1") (pin "2") (pinfunction "2_2") (pintype "passive"))
      (node (ref "JP1") (pin "1") (pinfunction "DTR_1") (pintype "passive"))
    )
    (net (code "88") (name "Net-(JP3-Pad1)") (class "Default")
      (node (ref "JP3") (pin "1") (pinfunction "1_1") (pintype "passive"))
      (node (ref "SRV2") (pin "1") (pinfunction "1_1") (pintype "passive"))
      (node (ref "SRV2") (pin "10") (pinfunction "10_10") (pintype "passive"))
      (node (ref "SRV2") (pin "11") (pinfunction "11_11") (pintype "passive"))
      (node (ref "SRV2") (pin "12") (pinfunction "12_12") (pintype "passive"))
      (node (ref "SRV2") (pin "2") (pinfunction "2_2") (pintype "passive"))
      (node (ref "SRV2") (pin "3") (pinfunction "3_3") (pintype "passive"))
      (node (ref "SRV2") (pin "4") (pinfunction "4_4") (pintype "passive"))
      (node (ref "SRV2") (pin "5") (pinfunction "5_5") (pintype "passive"))
      (node (ref "SRV2") (pin "6") (pinfunction "6_6") (pintype "passive"))
      (node (ref "SRV2") (pin "7") (pinfunction "7_7") (pintype "passive"))
      (node (ref "SRV2") (pin "8") (pinfunction "8_8") (pintype "passive"))
      (node (ref "SRV2") (pin "9") (pinfunction "9_9") (pintype "passive"))
    )
    (net (code "89") (name "Net-(U1-AREF)") (class "Default")
      (node (ref "C3") (pin "2") (pinfunction "2_2") (pintype "passive"))
      (node (ref "U1") (pin "98") (pinfunction "AREF_98") (pintype "bidirectional"))
    )
    (net (code "90") (name "Net-(U1-AVCC)") (class "Default")
      (node (ref "C15") (pin "1") (pinfunction "1_1") (pintype "passive"))
      (node (ref "L1") (pin "1") (pinfunction "1_1") (pintype "passive"))
      (node (ref "U1") (pin "100") (pinfunction "AVCC_100") (pintype "power_in"))
    )
    (net (code "91") (name "Net-(U1-XTAL1)") (class "Default")
      (node (ref "C10") (pin "1") (pinfunction "1_1") (pintype "passive"))
      (node (ref "U1") (pin "34") (pinfunction "XTAL1_34") (pintype "input"))
      (node (ref "Y1") (pin "2") (pinfunction "2_2") (pintype "passive"))
    )
    (net (code "92") (name "Net-(U1-XTAL2)") (class "Default")
      (node (ref "C9") (pin "1") (pinfunction "1_1") (pintype "passive"))
      (node (ref "U1") (pin "33") (pinfunction "XTAL2_33") (pintype "output"))
      (node (ref "Y1") (pin "1") (pinfunction "1_1") (pintype "passive"))
    )
    (net (code "93") (name "unconnected-(JP1-CTS-Pad5)") (class "Default")
      (node (ref "JP1") (pin "5") (pinfunction "CTS_5") (pintype "passive"))
    )
    (net (code "94") (name "unconnected-(PI-7-GPIO7-Pad7)") (class "Default")
      (node (ref "PI") (pin "7") (pinfunction "7-GPIO7_7") (pintype "bidirectional"))
    )
    (net (code "95") (name "unconnected-(PI-11-GPIO0-Pad11)") (class "Default")
      (node (ref "PI") (pin "11") (pinfunction "11-GPIO0_11") (pintype "bidirectional"))
    )
    (net (code "96") (name "unconnected-(PI-12-GPIO1-Pad12)") (class "Default")
      (node (ref "PI") (pin "12") (pinfunction "12-GPIO1_12") (pintype "bidirectional"))
    )
    (net (code "97") (name "unconnected-(PI-13-GPIO2-Pad13)") (class "Default")
      (node (ref "PI") (pin "13") (pinfunction "13-GPIO2_13") (pintype "bidirectional"))
    )
    (net (code "98") (name "unconnected-(PI-15-GPIO3-Pad15)") (class "Default")
      (node (ref "PI") (pin "15") (pinfunction "15-GPIO3_15") (pintype "bidirectional"))
    )
    (net (code "99") (name "unconnected-(PI-16-GPIO4-Pad16)") (class "Default")
      (node (ref "PI") (pin "16") (pinfunction "16-GPIO4_16") (pintype "bidirectional"))
    )
    (net (code "100") (name "unconnected-(PI-18-GPIO5-Pad18)") (class "Default")
      (node (ref "PI") (pin "18") (pinfunction "18-GPIO5_18") (pintype "bidirectional"))
    )
    (net (code "101") (name "unconnected-(PI-19-SPI-MOSI-Pad19)") (class "Default")
      (node (ref "PI") (pin "19") (pinfunction "19-SPI-MOSI_19") (pintype "bidirectional"))
    )
    (net (code "102") (name "unconnected-(PI-21-SPI-MISO-Pad21)") (class "Default")
      (node (ref "PI") (pin "21") (pinfunction "21-SPI-MISO_21") (pintype "bidirectional"))
    )
    (net (code "103") (name "unconnected-(PI-22-GPIO6-Pad22)") (class "Default")
      (node (ref "PI") (pin "22") (pinfunction "22-GPIO6_22") (pintype "bidirectional"))
    )
    (net (code "104") (name "unconnected-(PI-23-SPI-SCLK-Pad23)") (class "Default")
      (node (ref "PI") (pin "23") (pinfunction "23-SPI-SCLK_23") (pintype "bidirectional"))
    )
    (net (code "105") (name "unconnected-(PI-24-SPI-CE0-N-Pad24)") (class "Default")
      (node (ref "PI") (pin "24") (pinfunction "24-SPI-CE0-N_24") (pintype "bidirectional"))
    )
    (net (code "106") (name "unconnected-(PI-26-SPI-CE1-N-Pad26)") (class "Default")
      (node (ref "PI") (pin "26") (pinfunction "26-SPI-CE1-N_26") (pintype "bidirectional"))
    )
    (net (code "107") (name "unconnected-(U1-(ALE)PG2-Pad70)") (class "Default")
      (node (ref "U1") (pin "70") (pinfunction "(ALE)PG2_70") (pintype "bidirectional"))
    )
    (net (code "108") (name "unconnected-(U1-(OC0A{slash}OC1C{slash}PCINT7)PB7-Pad26)") (class "Default")
      (node (ref "U1") (pin "26") (pinfunction "(OC0A/OC1C/PCINT7)PB7_26") (pintype "bidirectional"))
    )
    (net (code "109") (name "unconnected-(U1-(OC0B)PG5-Pad1)") (class "Default")
      (node (ref "U1") (pin "1") (pinfunction "(OC0B)PG5_1") (pintype "bidirectional"))
    )
    (net (code "110") (name "unconnected-(U1-(OC1A{slash}PCINT5)PB5-Pad24)") (class "Default")
      (node (ref "U1") (pin "24") (pinfunction "(OC1A/PCINT5)PB5_24") (pintype "bidirectional"))
    )
    (net (code "111") (name "unconnected-(U1-(OC1B{slash}PCINT6)PB6-Pad25)") (class "Default")
      (node (ref "U1") (pin "25") (pinfunction "(OC1B/PCINT6)PB6_25") (pintype "bidirectional"))
    )
    (net (code "112") (name "unconnected-(U1-(OC2A{slash}PCINT4)PB4-Pad23)") (class "Default")
      (node (ref "U1") (pin "23") (pinfunction "(OC2A/PCINT4)PB4_23") (pintype "bidirectional"))
    )
    (net (code "113") (name "unconnected-(U1-(RD)PG1-Pad52)") (class "Default")
      (node (ref "U1") (pin "52") (pinfunction "(RD)PG1_52") (pintype "bidirectional"))
    )
    (net (code "114") (name "unconnected-(U1-(SS{slash}PCINT0)PB0-Pad19)") (class "Default")
      (node (ref "U1") (pin "19") (pinfunction "(SS/PCINT0)PB0_19") (pintype "bidirectional"))
    )
    (net (code "115") (name "unconnected-(U1-(TOSC1)PG4-Pad29)") (class "Default")
      (node (ref "U1") (pin "29") (pinfunction "(TOSC1)PG4_29") (pintype "bidirectional"))
    )
    (net (code "116") (name "unconnected-(U1-(TOSC2)PG3-Pad28)") (class "Default")
      (node (ref "U1") (pin "28") (pinfunction "(TOSC2)PG3_28") (pintype "bidirectional"))
    )
    (net (code "117") (name "unconnected-(U1-(WR)PG0-Pad51)") (class "Default")
      (node (ref "U1") (pin "51") (pinfunction "(WR)PG0_51") (pintype "bidirectional"))
    )
    (net (code "118") (name "unconnected-(U1-PH0(RXD2)-Pad12)") (class "Default")
      (node (ref "U1") (pin "12") (pinfunction "PH0(RXD2)_12") (pintype "bidirectional"))
    )
    (net (code "119") (name "unconnected-(U1-PH1(TXD2)-Pad13)") (class "Default")
      (node (ref "U1") (pin "13") (pinfunction "PH1(TXD2)_13") (pintype "bidirectional"))
    )
    (net (code "120") (name "unconnected-(U1-PJ2(XCK3{slash}PCINT11)-Pad65)") (class "Default")
      (node (ref "U1") (pin "65") (pinfunction "PJ2(XCK3/PCINT11)_65") (pintype "bidirectional"))
    )
    (net (code "121") (name "unconnected-(U1-PJ3(PCINT12)-Pad66)") (class "Default")
      (node (ref "U1") (pin "66") (pinfunction "PJ3(PCINT12)_66") (pintype "bidirectional"))
    )
    (net (code "122") (name "unconnected-(U1-PJ4(PCINT13)-Pad67)") (class "Default")
      (node (ref "U1") (pin "67") (pinfunction "PJ4(PCINT13)_67") (pintype "bidirectional"))
    )
    (net (code "123") (name "unconnected-(U1-PJ5(PCINT14)-Pad68)") (class "Default")
      (node (ref "U1") (pin "68") (pinfunction "PJ5(PCINT14)_68") (pintype "bidirectional"))
    )
    (net (code "124") (name "unconnected-(U1-PJ6(PCINT15)-Pad69)") (class "Default")
      (node (ref "U1") (pin "69") (pinfunction "PJ6(PCINT15)_69") (pintype "bidirectional"))
    )
    (net (code "125") (name "unconnected-(U1-PJ7-Pad79)") (class "Default")
      (node (ref "U1") (pin "79") (pinfunction "PJ7_79") (pintype "bidirectional"))
    )
    (net (code "126") (name "unconnected-(U3-NC-Pad3)") (class "Default")
      (node (ref "U3") (pin "3") (pinfunction "NC_3") (pintype "bidirectional"))
    )
    (net (code "127") (name "unconnected-(U3-NC-Pad18)") (class "Default")
      (node (ref "U3") (pin "18") (pinfunction "NC_18") (pintype "bidirectional"))
    )
    (net (code "128") (name "unconnected-(U4-NC-Pad3)") (class "Default")
      (node (ref "U4") (pin "3") (pinfunction "NC_3") (pintype "bidirectional"))
    )
    (net (code "129") (name "unconnected-(U4-NC-Pad18)") (class "Default")
      (node (ref "U4") (pin "18") (pinfunction "NC_18") (pintype "bidirectional"))
    )
  )
)
